# CAN-BUS_Shield_v1_2.net
KiCad netlist of a schematic drawn in EAGLE
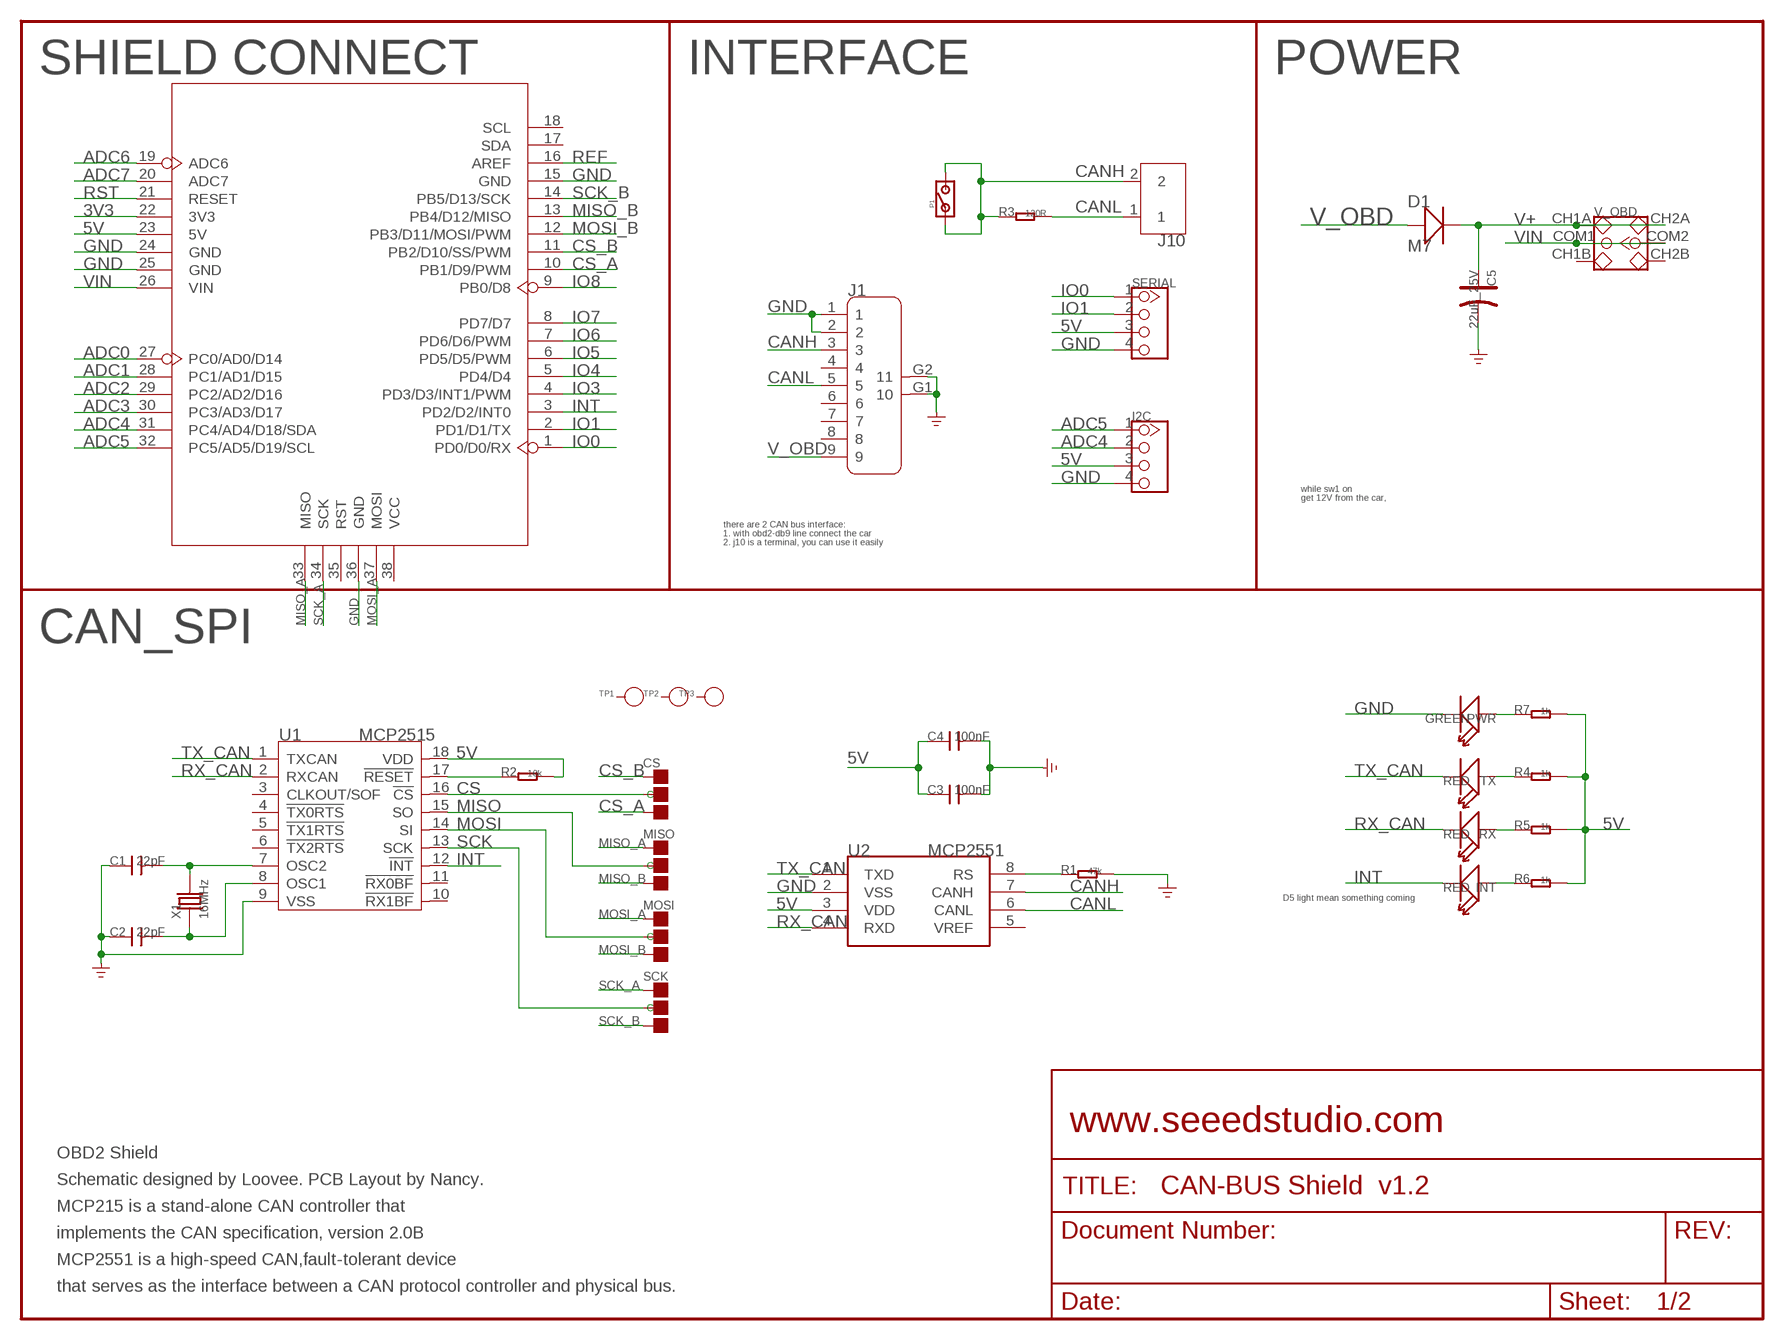
[diagram p0: schematic, sheet 1]

(export (version "E")
  (design (tool "Eeschema 10.0.6"))
  (components
    (comp (ref "C1")
      (value "22pF")
      (footprint "eagle-import:0603")
      (libsource (lib "eagle-import") (part "C-0603"))
    )
    (comp (ref "C2")
      (value "22pF")
      (footprint "eagle-import:0603")
      (libsource (lib "eagle-import") (part "C-0603"))
    )
    (comp (ref "C3")
      (value "100nF")
      (footprint "eagle-import:0603")
      (libsource (lib "eagle-import") (part "C-0603"))
    )
    (comp (ref "C4")
      (value "100nF")
      (footprint "eagle-import:0603")
      (libsource (lib "eagle-import") (part "C-0603"))
    )
    (comp (ref "C5")
      (value "22uF_25V")
      (footprint "eagle-import:ELECTRO-SMD-B-4.8MM")
      (libsource (lib "eagle-import") (part "CAP-ELECTRO-B"))
    )
    (comp (ref "CS")
      (value "PAD-JUMPER-3P-40*40")
      (footprint "eagle-import:3P-SMD-4.1X1.5")
      (libsource (lib "eagle-import") (part "PAD-JUMPER-3P-4040"))
    )
    (comp (ref "D1")
      (value "M7")
      (footprint "eagle-import:D2010")
      (libsource (lib "eagle-import") (part "D-SMA"))
    )
    (comp (ref "I2C")
      (value "TWIG-4P-2.0-2.0")
      (footprint "eagle-import:4P-2.0")
      (libsource (lib "eagle-import") (part "TWIG-4P-2.0-2.0"))
    )
    (comp (ref "INT")
      (value "RED")
      (footprint "eagle-import:LED-0603")
      (libsource (lib "eagle-import") (part "LED'0603'"))
    )
    (comp (ref "J1")
      (value "DB9'MEAL'")
      (footprint "eagle-import:DB9-MEAL")
      (libsource (lib "eagle-import") (part "DB9'MEAL'"))
    )
    (comp (ref "J10")
      (value "SCREW-TERMINAL-2P5.0")
      (footprint "eagle-import:2P-5.0")
      (libsource (lib "eagle-import") (part "SCREW-TERMINAL-2P5.0"))
    )
    (comp (ref "MISO")
      (value "PAD-JUMPER-3P-40*40")
      (footprint "eagle-import:3P-SMD-4.1X1.5")
      (libsource (lib "eagle-import") (part "PAD-JUMPER-3P-4040"))
    )
    (comp (ref "MOSI")
      (value "PAD-JUMPER-3P-40*40")
      (footprint "eagle-import:3P-SMD-4.1X1.5")
      (libsource (lib "eagle-import") (part "PAD-JUMPER-3P-4040"))
    )
    (comp (ref "P1")
      (value "PAD-JUMPER-2P")
      (footprint "eagle-import:2P-SMD-1.78X1.27")
      (libsource (lib "eagle-import") (part "PAD-JUMPER-2P"))
    )
    (comp (ref "PWR")
      (value "GREEN")
      (footprint "eagle-import:LED-0603")
      (libsource (lib "eagle-import") (part "LED'0603'"))
    )
    (comp (ref "R1")
      (value "47k")
      (footprint "eagle-import:0603")
      (libsource (lib "eagle-import") (part "R-0603"))
    )
    (comp (ref "R2")
      (value "10k")
      (footprint "eagle-import:0603")
      (libsource (lib "eagle-import") (part "R-0603"))
    )
    (comp (ref "R3")
      (value "120R")
      (footprint "eagle-import:0603")
      (libsource (lib "eagle-import") (part "R-0603"))
    )
    (comp (ref "R4")
      (value "1k")
      (footprint "eagle-import:0603")
      (libsource (lib "eagle-import") (part "R-0603"))
    )
    (comp (ref "R5")
      (value "1k")
      (footprint "eagle-import:0603")
      (libsource (lib "eagle-import") (part "R-0603"))
    )
    (comp (ref "R6")
      (value "1k")
      (footprint "eagle-import:0603")
      (libsource (lib "eagle-import") (part "R-0603"))
    )
    (comp (ref "R7")
      (value "1k")
      (footprint "eagle-import:0603")
      (libsource (lib "eagle-import") (part "R-0603"))
    )
    (comp (ref "RX")
      (value "RED")
      (footprint "eagle-import:LED-0603")
      (libsource (lib "eagle-import") (part "LED'0603'"))
    )
    (comp (ref "SCK")
      (value "PAD-JUMPER-3P-40*40")
      (footprint "eagle-import:3P-SMD-4.1X1.5")
      (libsource (lib "eagle-import") (part "PAD-JUMPER-3P-4040"))
    )
    (comp (ref "SERIAL")
      (value "TWIG-4P-2.0-2.0")
      (footprint "eagle-import:4P-2.0")
      (libsource (lib "eagle-import") (part "TWIG-4P-2.0-2.0"))
    )
    (comp (ref "TP1")
      (value "PAD-TEST-POINT'4545'")
      (footprint "eagle-import:TP_4545")
      (fields (field (name "PARTNO") "DNP"))
      (libsource (lib "eagle-import") (part "PAD-TEST-POINT'4545'"))
    )
    (comp (ref "TP2")
      (value "PAD-TEST-POINT'4545'")
      (footprint "eagle-import:TP_4545")
      (fields (field (name "PARTNO") "DNP"))
      (libsource (lib "eagle-import") (part "PAD-TEST-POINT'4545'"))
    )
    (comp (ref "TP3")
      (value "PAD-TEST-POINT'4545'")
      (footprint "eagle-import:TP_4545")
      (fields (field (name "PARTNO") "DNP"))
      (libsource (lib "eagle-import") (part "PAD-TEST-POINT'4545'"))
    )
    (comp (ref "TX")
      (value "RED")
      (footprint "eagle-import:LED-0603")
      (libsource (lib "eagle-import") (part "LED'0603'"))
    )
    (comp (ref "U1")
      (value "MCP2515")
      (footprint "eagle-import:SOIC18")
      (libsource (lib "eagle-import") (part "MCP2515-SOIC18"))
    )
    (comp (ref "U2")
      (value "MCP2551")
      (footprint "eagle-import:SOIC8-6.0")
      (libsource (lib "eagle-import") (part "MCP2551-SOIC8"))
    )
    (comp (ref "U4")
      (value "ARDUINO-38P'WITH/-SILK'")
      (footprint "eagle-import:ARDUINO-38P-WITH_-SILK-500519002")
      (libsource (lib "eagle-import") (part "ARDUINO-38P'WITH/-SILK'"))
    )
    (comp (ref "V_OBD")
      (value "SWITCH-2CH-6P")
      (footprint "eagle-import:6P-2CH-2.54-7.6X3.0")
      (libsource (lib "eagle-import") (part "SWITCH-2CH-6P"))
    )
    (comp (ref "X1")
      (value "16MHz")
      (footprint "eagle-import:HC49_S")
      (libsource (lib "eagle-import") (part "CRYSTAL-HC49S"))
    )
  )
  (nets
    (net (code "1") (name "3V3") (class "Default")
      (node (ref "U4") (pin "22") (pinfunction "3V3_22") (pintype "bidirectional"))
    )
    (net (code "2") (name "5V") (class "Default")
      (node (ref "C3") (pin "1") (pinfunction "1_1") (pintype "passive"))
      (node (ref "C4") (pin "1") (pinfunction "1_1") (pintype "passive"))
      (node (ref "I2C") (pin "3") (pinfunction "3_3") (pintype "bidirectional"))
      (node (ref "R2") (pin "2") (pinfunction "2_2") (pintype "passive"))
      (node (ref "R4") (pin "2") (pinfunction "2_2") (pintype "passive"))
      (node (ref "R5") (pin "2") (pinfunction "2_2") (pintype "passive"))
      (node (ref "R6") (pin "2") (pinfunction "2_2") (pintype "passive"))
      (node (ref "R7") (pin "2") (pinfunction "2_2") (pintype "passive"))
      (node (ref "SERIAL") (pin "3") (pinfunction "3_3") (pintype "bidirectional"))
      (node (ref "U1") (pin "18") (pinfunction "VDD_18") (pintype "power_in"))
      (node (ref "U2") (pin "3") (pinfunction "VDD_3") (pintype "bidirectional"))
      (node (ref "U4") (pin "23") (pinfunction "5V_23") (pintype "bidirectional"))
    )
    (net (code "3") (name "ADC0") (class "Default")
      (node (ref "U4") (pin "27") (pinfunction "PC0/AD0/D14_27") (pintype "bidirectional"))
    )
    (net (code "4") (name "ADC1") (class "Default")
      (node (ref "U4") (pin "28") (pinfunction "PC1/AD1/D15_28") (pintype "bidirectional"))
    )
    (net (code "5") (name "ADC2") (class "Default")
      (node (ref "U4") (pin "29") (pinfunction "PC2/AD2/D16_29") (pintype "bidirectional"))
    )
    (net (code "6") (name "ADC3") (class "Default")
      (node (ref "U4") (pin "30") (pinfunction "PC3/AD3/D17_30") (pintype "bidirectional"))
    )
    (net (code "7") (name "ADC4") (class "Default")
      (node (ref "I2C") (pin "2") (pinfunction "2_2") (pintype "bidirectional"))
      (node (ref "U4") (pin "31") (pinfunction "PC4/AD4/D18/SDA_31") (pintype "bidirectional"))
    )
    (net (code "8") (name "ADC5") (class "Default")
      (node (ref "I2C") (pin "1") (pinfunction "1_1") (pintype "bidirectional"))
      (node (ref "U4") (pin "32") (pinfunction "PC5/AD5/D19/SCL_32") (pintype "bidirectional"))
    )
    (net (code "9") (name "ADC6") (class "Default")
      (node (ref "U4") (pin "19") (pinfunction "ADC6_19") (pintype "bidirectional"))
    )
    (net (code "10") (name "ADC7") (class "Default")
      (node (ref "U4") (pin "20") (pinfunction "ADC7_20") (pintype "bidirectional"))
    )
    (net (code "11") (name "CANH") (class "Default")
      (node (ref "J1") (pin "3") (pinfunction "3_3") (pintype "bidirectional"))
      (node (ref "J10") (pin "2") (pinfunction "2_2") (pintype "bidirectional"))
      (node (ref "P1") (pin "1") (pinfunction "1_1") (pintype "bidirectional"))
      (node (ref "P1") (pin "2") (pinfunction "2_2") (pintype "bidirectional"))
      (node (ref "R3") (pin "1") (pinfunction "1_1") (pintype "passive"))
      (node (ref "U2") (pin "7") (pinfunction "CANH_7") (pintype "bidirectional"))
    )
    (net (code "12") (name "CANL") (class "Default")
      (node (ref "J1") (pin "5") (pinfunction "5_5") (pintype "bidirectional"))
      (node (ref "J10") (pin "1") (pinfunction "1_1") (pintype "bidirectional"))
      (node (ref "R3") (pin "2") (pinfunction "2_2") (pintype "passive"))
      (node (ref "U2") (pin "6") (pinfunction "CANL_6") (pintype "bidirectional"))
    )
    (net (code "13") (name "CS") (class "Default")
      (node (ref "CS") (pin "MM") (pinfunction "C_MM") (pintype "bidirectional"))
      (node (ref "U1") (pin "16") (pinfunction "~{CS}_16") (pintype "input"))
    )
    (net (code "14") (name "CS_A") (class "Default")
      (node (ref "CS") (pin "11") (pinfunction "R_11") (pintype "bidirectional"))
      (node (ref "U4") (pin "10") (pinfunction "PB1/D9/PWM_10") (pintype "bidirectional"))
    )
    (net (code "15") (name "CS_B") (class "Default")
      (node (ref "CS") (pin "00") (pinfunction "L_00") (pintype "bidirectional"))
      (node (ref "U4") (pin "11") (pinfunction "PB2/D10/SS/PWM_11") (pintype "bidirectional"))
    )
    (net (code "16") (name "GND") (class "Default")
      (node (ref "C1") (pin "1") (pinfunction "1_1") (pintype "passive"))
      (node (ref "C2") (pin "1") (pinfunction "1_1") (pintype "passive"))
      (node (ref "C3") (pin "2") (pinfunction "2_2") (pintype "passive"))
      (node (ref "C4") (pin "2") (pinfunction "2_2") (pintype "passive"))
      (node (ref "C5") (pin "-") (pinfunction "-_-") (pintype "passive"))
      (node (ref "I2C") (pin "4") (pinfunction "4_4") (pintype "bidirectional"))
      (node (ref "J1") (pin "1") (pinfunction "1_1") (pintype "bidirectional"))
      (node (ref "J1") (pin "2") (pinfunction "2_2") (pintype "bidirectional"))
      (node (ref "J1") (pin "G1") (pinfunction "10_G1") (pintype "bidirectional"))
      (node (ref "J1") (pin "G2") (pinfunction "11_G2") (pintype "bidirectional"))
      (node (ref "PWR") (pin "-") (pinfunction "-_-") (pintype "passive"))
      (node (ref "R1") (pin "2") (pinfunction "2_2") (pintype "passive"))
      (node (ref "SERIAL") (pin "4") (pinfunction "4_4") (pintype "bidirectional"))
      (node (ref "U1") (pin "9") (pinfunction "VSS_9") (pintype "power_in"))
      (node (ref "U2") (pin "2") (pinfunction "VSS_2") (pintype "bidirectional"))
      (node (ref "U4") (pin "15") (pinfunction "GND_15") (pintype "bidirectional"))
      (node (ref "U4") (pin "24") (pinfunction "GND_24") (pintype "bidirectional"))
      (node (ref "U4") (pin "25") (pinfunction "GND_25") (pintype "bidirectional"))
      (node (ref "U4") (pin "36") (pinfunction "GND_36") (pintype "bidirectional"))
    )
    (net (code "17") (name "INT") (class "Default")
      (node (ref "INT") (pin "-") (pinfunction "-_-") (pintype "passive"))
      (node (ref "U1") (pin "12") (pinfunction "~{INT}_12") (pintype "output"))
      (node (ref "U4") (pin "3") (pinfunction "PD2/D2/INT0_3") (pintype "bidirectional"))
    )
    (net (code "18") (name "IO0") (class "Default")
      (node (ref "SERIAL") (pin "1") (pinfunction "1_1") (pintype "bidirectional"))
      (node (ref "U4") (pin "1") (pinfunction "PD0/D0/RX_1") (pintype "bidirectional"))
    )
    (net (code "19") (name "IO1") (class "Default")
      (node (ref "SERIAL") (pin "2") (pinfunction "2_2") (pintype "bidirectional"))
      (node (ref "U4") (pin "2") (pinfunction "PD1/D1/TX_2") (pintype "bidirectional"))
    )
    (net (code "20") (name "IO3") (class "Default")
      (node (ref "U4") (pin "4") (pinfunction "PD3/D3/INT1/PWM_4") (pintype "bidirectional"))
    )
    (net (code "21") (name "IO4") (class "Default")
      (node (ref "U4") (pin "5") (pinfunction "PD4/D4_5") (pintype "bidirectional"))
    )
    (net (code "22") (name "IO5") (class "Default")
      (node (ref "U4") (pin "6") (pinfunction "PD5/D5/PWM_6") (pintype "bidirectional"))
    )
    (net (code "23") (name "IO6") (class "Default")
      (node (ref "U4") (pin "7") (pinfunction "PD6/D6/PWM_7") (pintype "bidirectional"))
    )
    (net (code "24") (name "IO7") (class "Default")
      (node (ref "U4") (pin "8") (pinfunction "PD7/D7_8") (pintype "bidirectional"))
    )
    (net (code "25") (name "IO8") (class "Default")
      (node (ref "U4") (pin "9") (pinfunction "PB0/D8_9") (pintype "bidirectional"))
    )
    (net (code "26") (name "MISO") (class "Default")
      (node (ref "MISO") (pin "MM") (pinfunction "C_MM") (pintype "bidirectional"))
      (node (ref "U1") (pin "15") (pinfunction "SO_15") (pintype "output"))
    )
    (net (code "27") (name "MISO_A") (class "Default")
      (node (ref "MISO") (pin "00") (pinfunction "L_00") (pintype "bidirectional"))
      (node (ref "U4") (pin "33") (pinfunction "MISO_33") (pintype "bidirectional"))
    )
    (net (code "28") (name "MISO_B") (class "Default")
      (node (ref "MISO") (pin "11") (pinfunction "R_11") (pintype "bidirectional"))
      (node (ref "U4") (pin "13") (pinfunction "PB4/D12/MISO_13") (pintype "bidirectional"))
    )
    (net (code "29") (name "MOSI") (class "Default")
      (node (ref "MOSI") (pin "MM") (pinfunction "C_MM") (pintype "bidirectional"))
      (node (ref "U1") (pin "14") (pinfunction "SI_14") (pintype "input"))
    )
    (net (code "30") (name "MOSI_A") (class "Default")
      (node (ref "MOSI") (pin "00") (pinfunction "L_00") (pintype "bidirectional"))
      (node (ref "U4") (pin "37") (pinfunction "MOSI_37") (pintype "bidirectional"))
    )
    (net (code "31") (name "MOSI_B") (class "Default")
      (node (ref "MOSI") (pin "11") (pinfunction "R_11") (pintype "bidirectional"))
      (node (ref "U4") (pin "12") (pinfunction "PB3/D11/MOSI/PWM_12") (pintype "bidirectional"))
    )
    (net (code "32") (name "Net-(INT-Pad+)") (class "Default")
      (node (ref "INT") (pin "+") (pinfunction "+_+") (pintype "passive"))
      (node (ref "R6") (pin "1") (pinfunction "1_1") (pintype "passive"))
    )
    (net (code "33") (name "Net-(PWR-Pad+)") (class "Default")
      (node (ref "PWR") (pin "+") (pinfunction "+_+") (pintype "passive"))
      (node (ref "R7") (pin "1") (pinfunction "1_1") (pintype "passive"))
    )
    (net (code "34") (name "Net-(R4-Pad1)") (class "Default")
      (node (ref "R4") (pin "1") (pinfunction "1_1") (pintype "passive"))
      (node (ref "TX") (pin "+") (pinfunction "+_+") (pintype "passive"))
    )
    (net (code "35") (name "Net-(R5-Pad1)") (class "Default")
      (node (ref "R5") (pin "1") (pinfunction "1_1") (pintype "passive"))
      (node (ref "RX") (pin "+") (pinfunction "+_+") (pintype "passive"))
    )
    (net (code "36") (name "Net-(U1-OSC1)") (class "Default")
      (node (ref "C2") (pin "2") (pinfunction "2_2") (pintype "passive"))
      (node (ref "U1") (pin "8") (pinfunction "OSC1_8") (pintype "input"))
      (node (ref "X1") (pin "1") (pinfunction "1_1") (pintype "passive"))
    )
    (net (code "37") (name "Net-(U1-OSC2)") (class "Default")
      (node (ref "C1") (pin "2") (pinfunction "2_2") (pintype "passive"))
      (node (ref "U1") (pin "7") (pinfunction "OSC2_7") (pintype "output"))
      (node (ref "X1") (pin "2") (pinfunction "2_2") (pintype "passive"))
    )
    (net (code "38") (name "Net-(U1-~{RESET})") (class "Default")
      (node (ref "R2") (pin "1") (pinfunction "1_1") (pintype "passive"))
      (node (ref "U1") (pin "17") (pinfunction "~{RESET}_17") (pintype "input"))
    )
    (net (code "39") (name "Net-(U2-RS)") (class "Default")
      (node (ref "R1") (pin "1") (pinfunction "1_1") (pintype "passive"))
      (node (ref "U2") (pin "8") (pinfunction "RS_8") (pintype "bidirectional"))
    )
    (net (code "40") (name "REF") (class "Default")
      (node (ref "U4") (pin "16") (pinfunction "AREF_16") (pintype "bidirectional"))
    )
    (net (code "41") (name "RST") (class "Default")
      (node (ref "U4") (pin "21") (pinfunction "RESET_21") (pintype "bidirectional"))
    )
    (net (code "42") (name "RX_CAN") (class "Default")
      (node (ref "RX") (pin "-") (pinfunction "-_-") (pintype "passive"))
      (node (ref "U1") (pin "2") (pinfunction "RXCAN_2") (pintype "input"))
      (node (ref "U2") (pin "4") (pinfunction "RXD_4") (pintype "bidirectional"))
    )
    (net (code "43") (name "SCK") (class "Default")
      (node (ref "SCK") (pin "MM") (pinfunction "C_MM") (pintype "bidirectional"))
      (node (ref "U1") (pin "13") (pinfunction "SCK_13") (pintype "input"))
    )
    (net (code "44") (name "SCK_A") (class "Default")
      (node (ref "SCK") (pin "00") (pinfunction "L_00") (pintype "bidirectional"))
      (node (ref "U4") (pin "34") (pinfunction "SCK_34") (pintype "bidirectional"))
    )
    (net (code "45") (name "SCK_B") (class "Default")
      (node (ref "SCK") (pin "11") (pinfunction "R_11") (pintype "bidirectional"))
      (node (ref "U4") (pin "14") (pinfunction "PB5/D13/SCK_14") (pintype "bidirectional"))
    )
    (net (code "46") (name "TX_CAN") (class "Default")
      (node (ref "TX") (pin "-") (pinfunction "-_-") (pintype "passive"))
      (node (ref "U1") (pin "1") (pinfunction "TXCAN_1") (pintype "output"))
      (node (ref "U2") (pin "1") (pinfunction "TXD_1") (pintype "bidirectional"))
    )
    (net (code "47") (name "V+") (class "Default")
      (node (ref "C5") (pin "+") (pinfunction "+_+") (pintype "passive"))
      (node (ref "D1") (pin "-") (pinfunction "-_-") (pintype "passive"))
      (node (ref "V_OBD") (pin "CH1A") (pinfunction "CH1A_CH1A") (pintype "bidirectional"))
      (node (ref "V_OBD") (pin "CH2A") (pinfunction "CH2A_CH2A") (pintype "bidirectional"))
    )
    (net (code "48") (name "VIN") (class "Default")
      (node (ref "U4") (pin "26") (pinfunction "VIN_26") (pintype "bidirectional"))
      (node (ref "V_OBD") (pin "COM1") (pinfunction "COM1_COM1") (pintype "bidirectional"))
      (node (ref "V_OBD") (pin "COM2") (pinfunction "COM2_COM2") (pintype "bidirectional"))
    )
    (net (code "49") (name "V_OBD") (class "Default")
      (node (ref "D1") (pin "+") (pinfunction "+_+") (pintype "passive"))
      (node (ref "J1") (pin "9") (pinfunction "9_9") (pintype "bidirectional"))
    )
    (net (code "50") (name "unconnected-(J1-Pad4)") (class "Default")
      (node (ref "J1") (pin "4") (pinfunction "4_4") (pintype "bidirectional"))
    )
    (net (code "51") (name "unconnected-(J1-Pad6)") (class "Default")
      (node (ref "J1") (pin "6") (pinfunction "6_6") (pintype "bidirectional"))
    )
    (net (code "52") (name "unconnected-(J1-Pad7)") (class "Default")
      (node (ref "J1") (pin "7") (pinfunction "7_7") (pintype "bidirectional"))
    )
    (net (code "53") (name "unconnected-(J1-Pad8)") (class "Default")
      (node (ref "J1") (pin "8") (pinfunction "8_8") (pintype "bidirectional"))
    )
    (net (code "54") (name "unconnected-(TP1-PadT)") (class "Default")
      (node (ref "TP1") (pin "T") (pinfunction "T_T") (pintype "bidirectional"))
    )
    (net (code "55") (name "unconnected-(TP2-PadT)") (class "Default")
      (node (ref "TP2") (pin "T") (pinfunction "T_T") (pintype "bidirectional"))
    )
    (net (code "56") (name "unconnected-(TP3-PadT)") (class "Default")
      (node (ref "TP3") (pin "T") (pinfunction "T_T") (pintype "bidirectional"))
    )
    (net (code "57") (name "unconnected-(U1-CLKOUT{slash}SOF-Pad3)") (class "Default")
      (node (ref "U1") (pin "3") (pinfunction "CLKOUT/SOF_3") (pintype "output"))
    )
    (net (code "58") (name "unconnected-(U1-~{RX0BF}-Pad11)") (class "Default")
      (node (ref "U1") (pin "11") (pinfunction "~{RX0BF}_11") (pintype "output"))
    )
    (net (code "59") (name "unconnected-(U1-~{RX1BF}-Pad10)") (class "Default")
      (node (ref "U1") (pin "10") (pinfunction "~{RX1BF}_10") (pintype "output"))
    )
    (net (code "60") (name "unconnected-(U1-~{TX0RTS}-Pad4)") (class "Default")
      (node (ref "U1") (pin "4") (pinfunction "~{TX0RTS}_4") (pintype "input"))
    )
    (net (code "61") (name "unconnected-(U1-~{TX1RTS}-Pad5)") (class "Default")
      (node (ref "U1") (pin "5") (pinfunction "~{TX1RTS}_5") (pintype "input"))
    )
    (net (code "62") (name "unconnected-(U1-~{TX2RTS}-Pad6)") (class "Default")
      (node (ref "U1") (pin "6") (pinfunction "~{TX2RTS}_6") (pintype "input"))
    )
    (net (code "63") (name "unconnected-(U2-VREF-Pad5)") (class "Default")
      (node (ref "U2") (pin "5") (pinfunction "VREF_5") (pintype "bidirectional"))
    )
    (net (code "64") (name "unconnected-(U4-RST-Pad35)") (class "Default")
      (node (ref "U4") (pin "35") (pinfunction "RST_35") (pintype "bidirectional"))
    )
    (net (code "65") (name "unconnected-(U4-SCL-Pad18)") (class "Default")
      (node (ref "U4") (pin "18") (pinfunction "SCL_18") (pintype "bidirectional"))
    )
    (net (code "66") (name "unconnected-(U4-SDA-Pad17)") (class "Default")
      (node (ref "U4") (pin "17") (pinfunction "SDA_17") (pintype "bidirectional"))
    )
    (net (code "67") (name "unconnected-(U4-VCC-Pad38)") (class "Default")
      (node (ref "U4") (pin "38") (pinfunction "VCC_38") (pintype "bidirectional"))
    )
    (net (code "68") (name "unconnected-(V_OBD-PadCH1B)") (class "Default")
      (node (ref "V_OBD") (pin "CH1B") (pinfunction "CH1B_CH1B") (pintype "bidirectional"))
    )
    (net (code "69") (name "unconnected-(V_OBD-PadCH2B)") (class "Default")
      (node (ref "V_OBD") (pin "CH2B") (pinfunction "CH2B_CH2B") (pintype "bidirectional"))
    )
  )
)
